# main.net
KiCad netlist of a schematic drawn in EAGLE
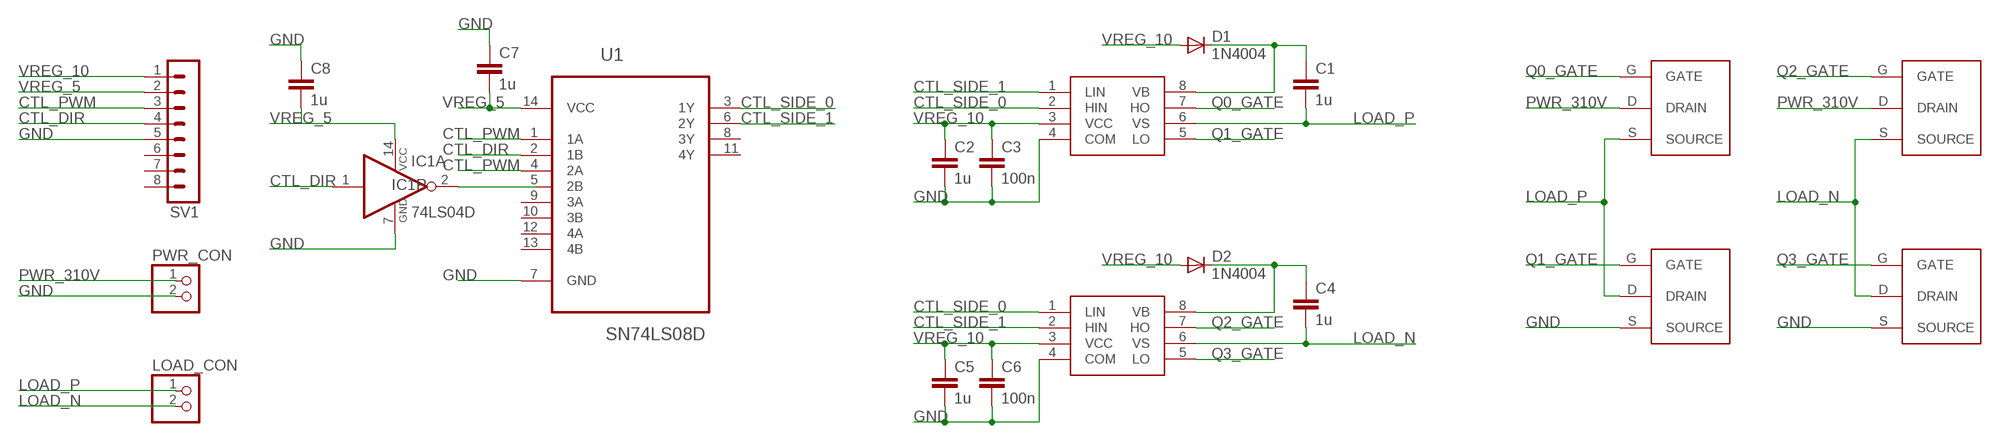
[diagram p0: schematic, sheet 1]

(export (version "E")
  (design (tool "Eeschema 10.0.6"))
  (components
    (comp (ref "C1")
      (value "1u")
      (footprint "eagle-import:C1206")
      (libsource (lib "eagle-import") (part "C-EUC1206"))
    )
    (comp (ref "C2")
      (value "1u")
      (footprint "eagle-import:C1206")
      (libsource (lib "eagle-import") (part "C-EUC1206"))
    )
    (comp (ref "C3")
      (value "100n")
      (footprint "eagle-import:C1206")
      (libsource (lib "eagle-import") (part "C-EUC1206"))
    )
    (comp (ref "C4")
      (value "1u")
      (footprint "eagle-import:C1206")
      (libsource (lib "eagle-import") (part "C-EUC1206"))
    )
    (comp (ref "C5")
      (value "1u")
      (footprint "eagle-import:C1206")
      (libsource (lib "eagle-import") (part "C-EUC1206"))
    )
    (comp (ref "C6")
      (value "100n")
      (footprint "eagle-import:C1206")
      (libsource (lib "eagle-import") (part "C-EUC1206"))
    )
    (comp (ref "C7")
      (value "1u")
      (footprint "eagle-import:C1206")
      (libsource (lib "eagle-import") (part "C-EUC1206"))
    )
    (comp (ref "C8")
      (value "1u")
      (footprint "eagle-import:C1206")
      (libsource (lib "eagle-import") (part "C-EUC1206"))
    )
    (comp (ref "D1")
      (value "1N4004")
      (footprint "eagle-import:DO41-10")
      (libsource (lib "eagle-import") (part "1N4004"))
    )
    (comp (ref "D2")
      (value "1N4004")
      (footprint "eagle-import:DO41-10")
      (libsource (lib "eagle-import") (part "1N4004"))
    )
    (comp (ref "IC1")
      (value "74LS04D")
      (footprint "eagle-import:SO14")
      (libsource (lib "eagle-import") (part "7404DLS"))
    )
    (comp (ref "IR2304_0")
      (value "IR2304")
      (footprint "eagle-import:SOIC8")
      (libsource (lib "eagle-import") (part "IR2304"))
    )
    (comp (ref "IR2304_1")
      (value "IR2304")
      (footprint "eagle-import:SOIC8")
      (libsource (lib "eagle-import") (part "IR2304"))
    )
    (comp (ref "LOAD_CON")
      (value "PINHD-1X2")
      (footprint "eagle-import:1X02")
      (libsource (lib "eagle-import") (part "PINHD-1X2"))
    )
    (comp (ref "PWR_CON")
      (value "PINHD-1X2")
      (footprint "eagle-import:1X02")
      (libsource (lib "eagle-import") (part "PINHD-1X2"))
    )
    (comp (ref "Q1")
      (value "IRFP460A")
      (footprint "eagle-import:TO247BV")
      (libsource (lib "eagle-import") (part "IRFP460A"))
    )
    (comp (ref "Q2")
      (value "IRFP460A")
      (footprint "eagle-import:TO247BV")
      (libsource (lib "eagle-import") (part "IRFP460A"))
    )
    (comp (ref "Q3")
      (value "IRFP460A")
      (footprint "eagle-import:TO247BV")
      (libsource (lib "eagle-import") (part "IRFP460A"))
    )
    (comp (ref "Q4")
      (value "IRFP460A")
      (footprint "eagle-import:TO247BV")
      (libsource (lib "eagle-import") (part "IRFP460A"))
    )
    (comp (ref "SV1")
      (value "MA08-1")
      (footprint "eagle-import:MA08-1")
      (libsource (lib "eagle-import") (part "MA08-1"))
    )
    (comp (ref "U1")
      (value "SN74LS08D")
      (footprint "eagle-import:SOIC127P600X175-14N")
      (libsource (lib "eagle-import") (part "SN74LS08D"))
    )
  )
  (nets
    (net (code "1") (name "/CTL_DIR") (class "Default")
      (node (ref "IC1") (pin "1") (pinfunction "I_1") (pintype "input"))
      (node (ref "SV1") (pin "4") (pinfunction "4_4") (pintype "passive"))
      (node (ref "U1") (pin "2") (pinfunction "1B_2") (pintype "input"))
    )
    (net (code "2") (name "/CTL_PWM") (class "Default")
      (node (ref "SV1") (pin "3") (pinfunction "3_3") (pintype "passive"))
      (node (ref "U1") (pin "1") (pinfunction "1A_1") (pintype "input"))
      (node (ref "U1") (pin "4") (pinfunction "2A_4") (pintype "input"))
    )
    (net (code "3") (name "/CTL_SIDE_0") (class "Default")
      (node (ref "IR2304_0") (pin "2") (pinfunction "HIN_2") (pintype "input"))
      (node (ref "IR2304_1") (pin "1") (pinfunction "LIN_1") (pintype "input"))
      (node (ref "U1") (pin "3") (pinfunction "1Y_3") (pintype "output"))
    )
    (net (code "4") (name "/CTL_SIDE_1") (class "Default")
      (node (ref "IR2304_0") (pin "1") (pinfunction "LIN_1") (pintype "input"))
      (node (ref "IR2304_1") (pin "2") (pinfunction "HIN_2") (pintype "input"))
      (node (ref "U1") (pin "6") (pinfunction "2Y_6") (pintype "output"))
    )
    (net (code "5") (name "/GND") (class "Default")
      (node (ref "C2") (pin "2") (pinfunction "2_2") (pintype "passive"))
      (node (ref "C3") (pin "2") (pinfunction "2_2") (pintype "passive"))
      (node (ref "C5") (pin "2") (pinfunction "2_2") (pintype "passive"))
      (node (ref "C6") (pin "2") (pinfunction "2_2") (pintype "passive"))
      (node (ref "C7") (pin "1") (pinfunction "1_1") (pintype "passive"))
      (node (ref "C8") (pin "1") (pinfunction "1_1") (pintype "passive"))
      (node (ref "IC1") (pin "7") (pinfunction "GND_7") (pintype "power_in"))
      (node (ref "IR2304_0") (pin "4") (pinfunction "COM_4") (pintype "power_in"))
      (node (ref "IR2304_1") (pin "4") (pinfunction "COM_4") (pintype "power_in"))
      (node (ref "PWR_CON") (pin "2") (pinfunction "2_2") (pintype "passive"))
      (node (ref "Q3") (pin "S") (pinfunction "SOURCE_S") (pintype "power_in"))
      (node (ref "Q4") (pin "S") (pinfunction "SOURCE_S") (pintype "power_in"))
      (node (ref "SV1") (pin "5") (pinfunction "5_5") (pintype "passive"))
      (node (ref "U1") (pin "7") (pinfunction "GND_7") (pintype "passive"))
    )
    (net (code "6") (name "/LOAD_N") (class "Default")
      (node (ref "C4") (pin "2") (pinfunction "2_2") (pintype "passive"))
      (node (ref "IR2304_1") (pin "6") (pinfunction "VS_6") (pintype "bidirectional"))
      (node (ref "LOAD_CON") (pin "2") (pinfunction "2_2") (pintype "passive"))
      (node (ref "Q2") (pin "S") (pinfunction "SOURCE_S") (pintype "power_in"))
      (node (ref "Q4") (pin "D") (pinfunction "DRAIN_D") (pintype "power_in"))
    )
    (net (code "7") (name "/LOAD_P") (class "Default")
      (node (ref "C1") (pin "2") (pinfunction "2_2") (pintype "passive"))
      (node (ref "IR2304_0") (pin "6") (pinfunction "VS_6") (pintype "bidirectional"))
      (node (ref "LOAD_CON") (pin "1") (pinfunction "1_1") (pintype "passive"))
      (node (ref "Q1") (pin "S") (pinfunction "SOURCE_S") (pintype "power_in"))
      (node (ref "Q3") (pin "D") (pinfunction "DRAIN_D") (pintype "power_in"))
    )
    (net (code "8") (name "/PWR_310V") (class "Default")
      (node (ref "PWR_CON") (pin "1") (pinfunction "1_1") (pintype "passive"))
      (node (ref "Q1") (pin "D") (pinfunction "DRAIN_D") (pintype "power_in"))
      (node (ref "Q2") (pin "D") (pinfunction "DRAIN_D") (pintype "power_in"))
    )
    (net (code "9") (name "/Q0_GATE") (class "Default")
      (node (ref "IR2304_0") (pin "7") (pinfunction "HO_7") (pintype "output"))
      (node (ref "Q1") (pin "G") (pinfunction "GATE_G") (pintype "input"))
    )
    (net (code "10") (name "/Q1_GATE") (class "Default")
      (node (ref "IR2304_0") (pin "5") (pinfunction "LO_5") (pintype "output"))
      (node (ref "Q3") (pin "G") (pinfunction "GATE_G") (pintype "input"))
    )
    (net (code "11") (name "/Q2_GATE") (class "Default")
      (node (ref "IR2304_1") (pin "7") (pinfunction "HO_7") (pintype "output"))
      (node (ref "Q2") (pin "G") (pinfunction "GATE_G") (pintype "input"))
    )
    (net (code "12") (name "/Q3_GATE") (class "Default")
      (node (ref "IR2304_1") (pin "5") (pinfunction "LO_5") (pintype "output"))
      (node (ref "Q4") (pin "G") (pinfunction "GATE_G") (pintype "input"))
    )
    (net (code "13") (name "/VREG_5") (class "Default")
      (node (ref "C7") (pin "2") (pinfunction "2_2") (pintype "passive"))
      (node (ref "IC1") (pin "14") (pinfunction "VCC_14") (pintype "power_in"))
      (node (ref "SV1") (pin "2") (pinfunction "2_2") (pintype "passive"))
      (node (ref "U1") (pin "14") (pinfunction "VCC_14") (pintype "power_in"))
    )
    (net (code "14") (name "/VREG_10") (class "Default")
      (node (ref "C2") (pin "1") (pinfunction "1_1") (pintype "passive"))
      (node (ref "C3") (pin "1") (pinfunction "1_1") (pintype "passive"))
      (node (ref "C5") (pin "1") (pinfunction "1_1") (pintype "passive"))
      (node (ref "C6") (pin "1") (pinfunction "1_1") (pintype "passive"))
      (node (ref "D1") (pin "A") (pinfunction "A_A") (pintype "passive"))
      (node (ref "D2") (pin "A") (pinfunction "A_A") (pintype "passive"))
      (node (ref "IR2304_0") (pin "3") (pinfunction "VCC_3") (pintype "power_in"))
      (node (ref "IR2304_1") (pin "3") (pinfunction "VCC_3") (pintype "power_in"))
      (node (ref "SV1") (pin "1") (pinfunction "1_1") (pintype "passive"))
    )
    (net (code "15") (name "Net-(IR2304_0-VB)") (class "Default")
      (node (ref "C1") (pin "1") (pinfunction "1_1") (pintype "passive"))
      (node (ref "D1") (pin "C") (pinfunction "C_C") (pintype "passive"))
      (node (ref "IR2304_0") (pin "8") (pinfunction "VB_8") (pintype "bidirectional"))
    )
    (net (code "16") (name "Net-(IR2304_1-VB)") (class "Default")
      (node (ref "C4") (pin "1") (pinfunction "1_1") (pintype "passive"))
      (node (ref "D2") (pin "C") (pinfunction "C_C") (pintype "passive"))
      (node (ref "IR2304_1") (pin "8") (pinfunction "VB_8") (pintype "bidirectional"))
    )
    (net (code "17") (name "unconnected-(C8-Pad2)") (class "Default")
      (node (ref "C8") (pin "2") (pinfunction "2_2") (pintype "passive"))
    )
    (net (code "18") (name "unconnected-(IC1A-O-Pad2)") (class "Default")
      (node (ref "IC1") (pin "2") (pinfunction "O_2") (pintype "output"))
    )
    (net (code "19") (name "unconnected-(SV1-Pad6)") (class "Default")
      (node (ref "SV1") (pin "6") (pinfunction "6_6") (pintype "passive"))
    )
    (net (code "20") (name "unconnected-(SV1-Pad7)") (class "Default")
      (node (ref "SV1") (pin "7") (pinfunction "7_7") (pintype "passive"))
    )
    (net (code "21") (name "unconnected-(SV1-Pad8)") (class "Default")
      (node (ref "SV1") (pin "8") (pinfunction "8_8") (pintype "passive"))
    )
    (net (code "22") (name "unconnected-(U1-2B-Pad5)") (class "Default")
      (node (ref "U1") (pin "5") (pinfunction "2B_5") (pintype "input"))
    )
    (net (code "23") (name "unconnected-(U1-3A-Pad9)") (class "Default")
      (node (ref "U1") (pin "9") (pinfunction "3A_9") (pintype "input"))
    )
    (net (code "24") (name "unconnected-(U1-3B-Pad10)") (class "Default")
      (node (ref "U1") (pin "10") (pinfunction "3B_10") (pintype "input"))
    )
    (net (code "25") (name "unconnected-(U1-3Y-Pad8)") (class "Default")
      (node (ref "U1") (pin "8") (pinfunction "3Y_8") (pintype "output"))
    )
    (net (code "26") (name "unconnected-(U1-4A-Pad12)") (class "Default")
      (node (ref "U1") (pin "12") (pinfunction "4A_12") (pintype "input"))
    )
    (net (code "27") (name "unconnected-(U1-4B-Pad13)") (class "Default")
      (node (ref "U1") (pin "13") (pinfunction "4B_13") (pintype "input"))
    )
    (net (code "28") (name "unconnected-(U1-4Y-Pad11)") (class "Default")
      (node (ref "U1") (pin "11") (pinfunction "4Y_11") (pintype "output"))
    )
  )
)
